# Adafruit_2_4in_TFT_FeatherWing.net
KiCad netlist of a schematic drawn in EAGLE
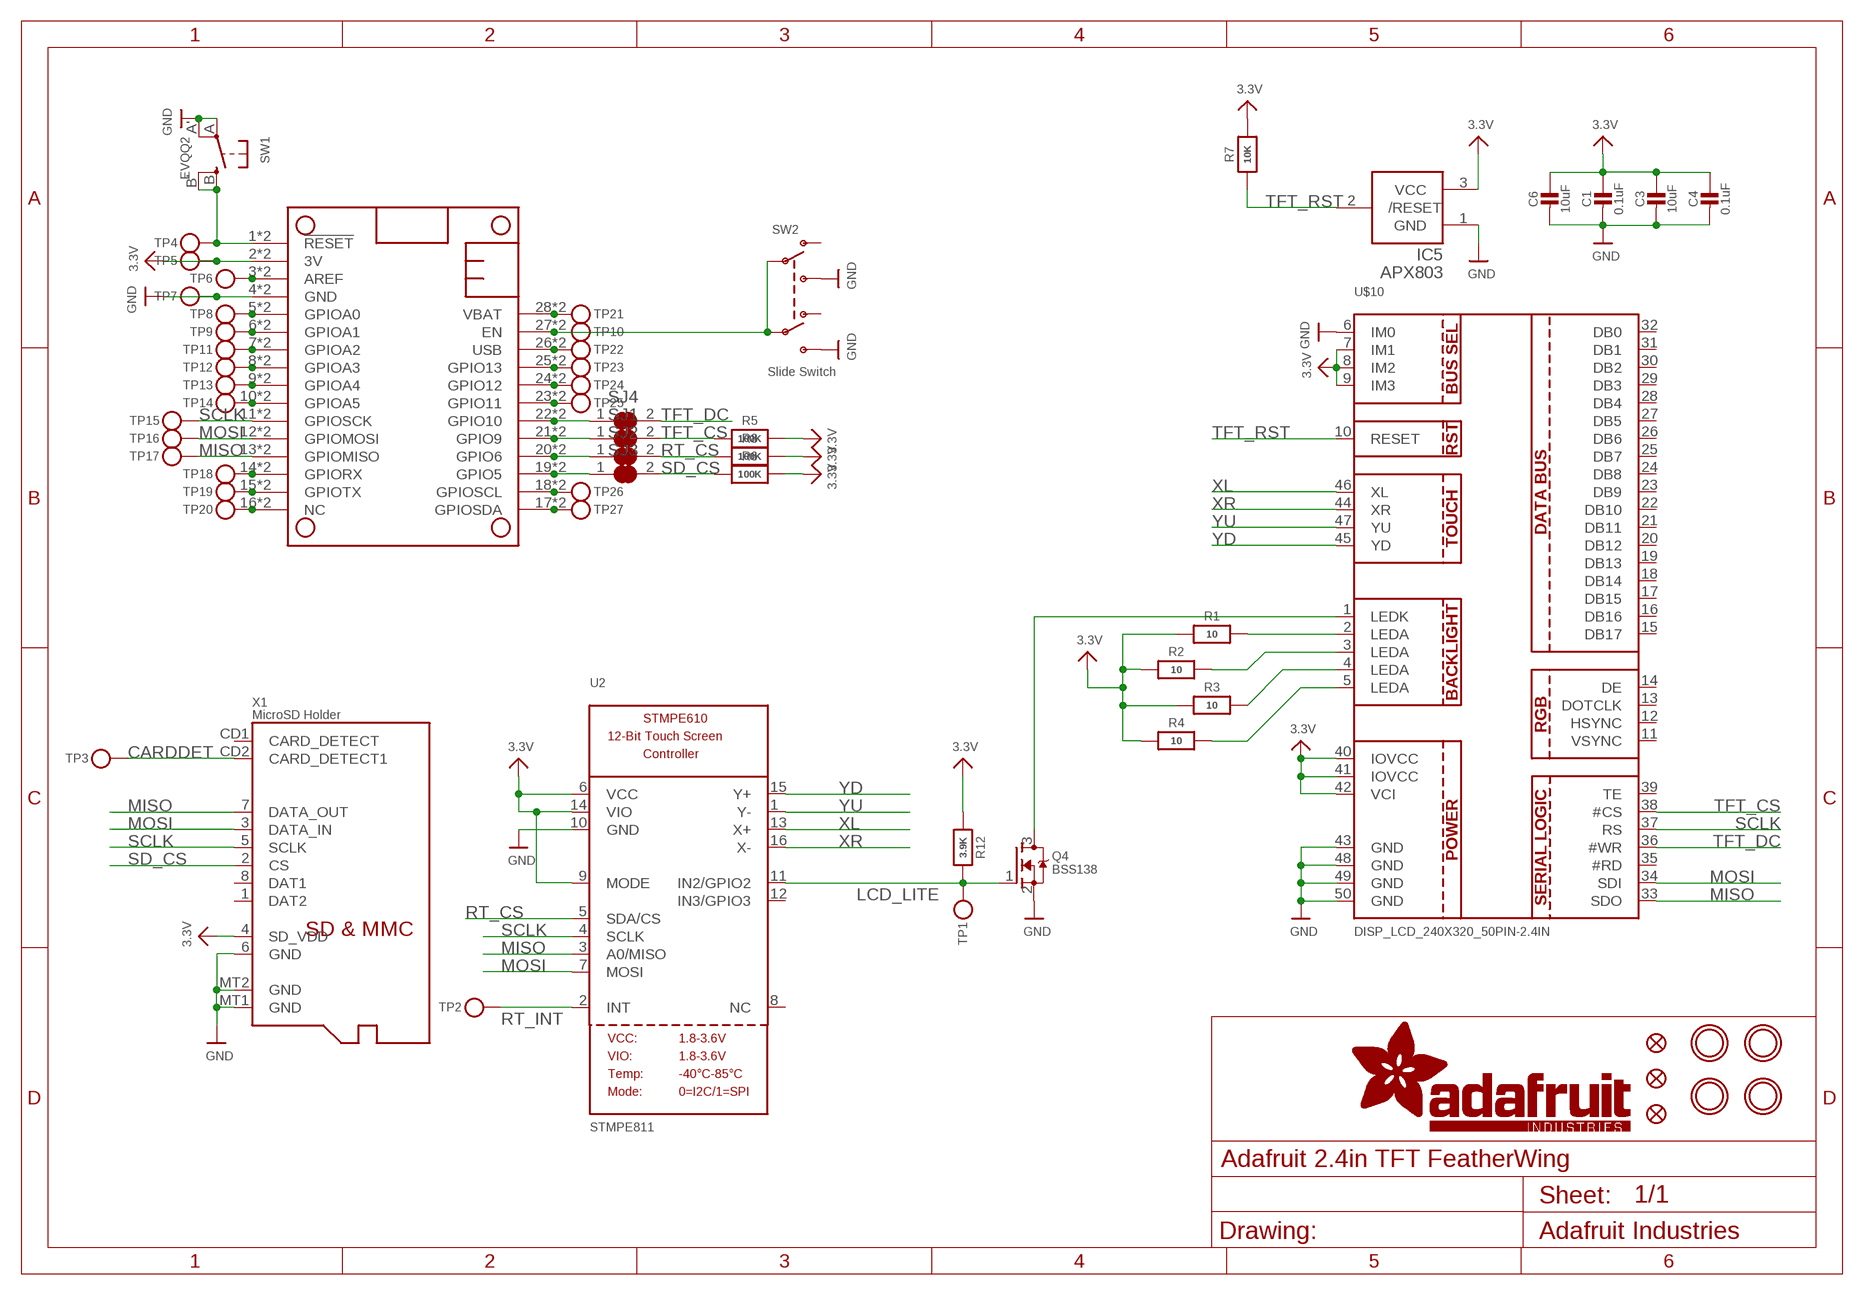
[diagram p0: schematic, sheet 1]

(export (version "E")
  (design (tool "Eeschema 10.0.6"))
  (components
    (comp (ref "C1")
      (value "0.1uF")
      (footprint "eagle-import:0805-NO")
      (libsource (lib "eagle-import") (part "CAP_CERAMIC0805-NOOUTLINE"))
    )
    (comp (ref "C3")
      (value "10uF")
      (footprint "eagle-import:0805-NO")
      (libsource (lib "eagle-import") (part "CAP_CERAMIC0805-NOOUTLINE"))
    )
    (comp (ref "C4")
      (value "0.1uF")
      (footprint "eagle-import:0805-NO")
      (libsource (lib "eagle-import") (part "CAP_CERAMIC0805-NOOUTLINE"))
    )
    (comp (ref "C6")
      (value "10uF")
      (footprint "eagle-import:0805-NO")
      (libsource (lib "eagle-import") (part "CAP_CERAMIC0805-NOOUTLINE"))
    )
    (comp (ref "FID1")
      (value "FIDUCIAL\"\"")
      (footprint "eagle-import:FIDUCIAL_1MM")
      (libsource (lib "eagle-import") (part "FIDUCIAL{dblquote}{dblquote}"))
    )
    (comp (ref "FID2")
      (value "FIDUCIAL\"\"")
      (footprint "eagle-import:FIDUCIAL_1MM")
      (libsource (lib "eagle-import") (part "FIDUCIAL{dblquote}{dblquote}"))
    )
    (comp (ref "FID3")
      (value "FIDUCIAL\"\"")
      (footprint "eagle-import:FIDUCIAL_1MM")
      (libsource (lib "eagle-import") (part "FIDUCIAL{dblquote}{dblquote}"))
    )
    (comp (ref "IC5")
      (value "APX803")
      (footprint "eagle-import:SOT23")
      (libsource (lib "eagle-import") (part "AXP083-SAG"))
    )
    (comp (ref "MS2")
      (value "FEATHERWING_SMTDUAL")
      (footprint "eagle-import:FEATHERWING_SMT2")
      (libsource (lib "eagle-import") (part "FEATHERWING_SMTDUAL"))
    )
    (comp (ref "Q4")
      (value "BSS138")
      (footprint "eagle-import:SOT23-WIDE")
      (libsource (lib "eagle-import") (part "MOSFET-NWIDE"))
    )
    (comp (ref "R1")
      (value "10")
      (footprint "eagle-import:0805-NO")
      (libsource (lib "eagle-import") (part "RESISTOR0805_NOOUTLINE"))
    )
    (comp (ref "R2")
      (value "10")
      (footprint "eagle-import:0805-NO")
      (libsource (lib "eagle-import") (part "RESISTOR0805_NOOUTLINE"))
    )
    (comp (ref "R3")
      (value "10")
      (footprint "eagle-import:0805-NO")
      (libsource (lib "eagle-import") (part "RESISTOR0805_NOOUTLINE"))
    )
    (comp (ref "R4")
      (value "10")
      (footprint "eagle-import:0805-NO")
      (libsource (lib "eagle-import") (part "RESISTOR0805_NOOUTLINE"))
    )
    (comp (ref "R5")
      (value "100K")
      (footprint "eagle-import:0805-NO")
      (libsource (lib "eagle-import") (part "RESISTOR0805_NOOUTLINE"))
    )
    (comp (ref "R6")
      (value "100K")
      (footprint "eagle-import:0805-NO")
      (libsource (lib "eagle-import") (part "RESISTOR0805_NOOUTLINE"))
    )
    (comp (ref "R7")
      (value "10K")
      (footprint "eagle-import:0805-NO")
      (libsource (lib "eagle-import") (part "RESISTOR0805_NOOUTLINE"))
    )
    (comp (ref "R8")
      (value "100K")
      (footprint "eagle-import:0805-NO")
      (libsource (lib "eagle-import") (part "RESISTOR0805_NOOUTLINE"))
    )
    (comp (ref "R12")
      (value "3.9K")
      (footprint "eagle-import:0805-NO")
      (libsource (lib "eagle-import") (part "RESISTOR0805_NOOUTLINE"))
    )
    (comp (ref "SJ1")
      (value "SOLDERJUMPER_CLOSED")
      (footprint "eagle-import:SOLDERJUMPER_CLOSEDWIRE")
      (libsource (lib "eagle-import") (part "SOLDERJUMPER_CLOSED"))
    )
    (comp (ref "SJ2")
      (value "SOLDERJUMPER_CLOSED")
      (footprint "eagle-import:SOLDERJUMPER_CLOSEDWIRE")
      (libsource (lib "eagle-import") (part "SOLDERJUMPER_CLOSED"))
    )
    (comp (ref "SJ3")
      (value "SOLDERJUMPER_CLOSED")
      (footprint "eagle-import:SOLDERJUMPER_CLOSEDWIRE")
      (libsource (lib "eagle-import") (part "SOLDERJUMPER_CLOSED"))
    )
    (comp (ref "SJ4")
      (value "SOLDERJUMPER_CLOSED")
      (footprint "eagle-import:SOLDERJUMPER_CLOSEDWIRE")
      (libsource (lib "eagle-import") (part "SOLDERJUMPER_CLOSED"))
    )
    (comp (ref "SW1")
      (value "EVQQ2")
      (footprint "eagle-import:EVQ-Q2_SMALLER")
      (libsource (lib "eagle-import") (part "SWITCH_TACT_SMT_EVQQ2_SMALL"))
    )
    (comp (ref "SW2")
      (value "Slide Switch")
      (footprint "eagle-import:EG1390")
      (libsource (lib "eagle-import") (part "SWITCH_DPDTEG1390"))
    )
    (comp (ref "TP1")
      (value "TESTPOINTPAD2MM")
      (footprint "eagle-import:TESTPOINT_PAD_2MM")
      (libsource (lib "eagle-import") (part "TESTPOINTPAD2MM"))
    )
    (comp (ref "TP2")
      (value "TESTPOINTPAD2MM")
      (footprint "eagle-import:TESTPOINT_PAD_2MM")
      (libsource (lib "eagle-import") (part "TESTPOINTPAD2MM"))
    )
    (comp (ref "TP3")
      (value "TESTPOINTPAD2MM")
      (footprint "eagle-import:TESTPOINT_PAD_2MM")
      (libsource (lib "eagle-import") (part "TESTPOINTPAD2MM"))
    )
    (comp (ref "TP4")
      (value "TESTPOINTPAD2MM")
      (footprint "eagle-import:TESTPOINT_PAD_2MM")
      (libsource (lib "eagle-import") (part "TESTPOINTPAD2MM"))
    )
    (comp (ref "TP5")
      (value "TESTPOINTPAD2MM")
      (footprint "eagle-import:TESTPOINT_PAD_2MM")
      (libsource (lib "eagle-import") (part "TESTPOINTPAD2MM"))
    )
    (comp (ref "TP6")
      (value "TESTPOINTPAD2MM")
      (footprint "eagle-import:TESTPOINT_PAD_2MM")
      (libsource (lib "eagle-import") (part "TESTPOINTPAD2MM"))
    )
    (comp (ref "TP7")
      (value "TESTPOINTPAD2MM")
      (footprint "eagle-import:TESTPOINT_PAD_2MM")
      (libsource (lib "eagle-import") (part "TESTPOINTPAD2MM"))
    )
    (comp (ref "TP8")
      (value "TESTPOINTPAD2MM")
      (footprint "eagle-import:TESTPOINT_PAD_2MM")
      (libsource (lib "eagle-import") (part "TESTPOINTPAD2MM"))
    )
    (comp (ref "TP9")
      (value "TESTPOINTPAD2MM")
      (footprint "eagle-import:TESTPOINT_PAD_2MM")
      (libsource (lib "eagle-import") (part "TESTPOINTPAD2MM"))
    )
    (comp (ref "TP10")
      (value "TESTPOINTPAD2MM")
      (footprint "eagle-import:TESTPOINT_PAD_2MM")
      (libsource (lib "eagle-import") (part "TESTPOINTPAD2MM"))
    )
    (comp (ref "TP11")
      (value "TESTPOINTPAD2MM")
      (footprint "eagle-import:TESTPOINT_PAD_2MM")
      (libsource (lib "eagle-import") (part "TESTPOINTPAD2MM"))
    )
    (comp (ref "TP12")
      (value "TESTPOINTPAD2MM")
      (footprint "eagle-import:TESTPOINT_PAD_2MM")
      (libsource (lib "eagle-import") (part "TESTPOINTPAD2MM"))
    )
    (comp (ref "TP13")
      (value "TESTPOINTPAD2MM")
      (footprint "eagle-import:TESTPOINT_PAD_2MM")
      (libsource (lib "eagle-import") (part "TESTPOINTPAD2MM"))
    )
    (comp (ref "TP14")
      (value "TESTPOINTPAD2MM")
      (footprint "eagle-import:TESTPOINT_PAD_2MM")
      (libsource (lib "eagle-import") (part "TESTPOINTPAD2MM"))
    )
    (comp (ref "TP15")
      (value "TESTPOINTPAD2MM")
      (footprint "eagle-import:TESTPOINT_PAD_2MM")
      (libsource (lib "eagle-import") (part "TESTPOINTPAD2MM"))
    )
    (comp (ref "TP16")
      (value "TESTPOINTPAD2MM")
      (footprint "eagle-import:TESTPOINT_PAD_2MM")
      (libsource (lib "eagle-import") (part "TESTPOINTPAD2MM"))
    )
    (comp (ref "TP17")
      (value "TESTPOINTPAD2MM")
      (footprint "eagle-import:TESTPOINT_PAD_2MM")
      (libsource (lib "eagle-import") (part "TESTPOINTPAD2MM"))
    )
    (comp (ref "TP18")
      (value "TESTPOINTPAD2MM")
      (footprint "eagle-import:TESTPOINT_PAD_2MM")
      (libsource (lib "eagle-import") (part "TESTPOINTPAD2MM"))
    )
    (comp (ref "TP19")
      (value "TESTPOINTPAD2MM")
      (footprint "eagle-import:TESTPOINT_PAD_2MM")
      (libsource (lib "eagle-import") (part "TESTPOINTPAD2MM"))
    )
    (comp (ref "TP20")
      (value "TESTPOINTPAD2MM")
      (footprint "eagle-import:TESTPOINT_PAD_2MM")
      (libsource (lib "eagle-import") (part "TESTPOINTPAD2MM"))
    )
    (comp (ref "TP21")
      (value "TESTPOINTPAD2MM")
      (footprint "eagle-import:TESTPOINT_PAD_2MM")
      (libsource (lib "eagle-import") (part "TESTPOINTPAD2MM"))
    )
    (comp (ref "TP22")
      (value "TESTPOINTPAD2MM")
      (footprint "eagle-import:TESTPOINT_PAD_2MM")
      (libsource (lib "eagle-import") (part "TESTPOINTPAD2MM"))
    )
    (comp (ref "TP23")
      (value "TESTPOINTPAD2MM")
      (footprint "eagle-import:TESTPOINT_PAD_2MM")
      (libsource (lib "eagle-import") (part "TESTPOINTPAD2MM"))
    )
    (comp (ref "TP24")
      (value "TESTPOINTPAD2MM")
      (footprint "eagle-import:TESTPOINT_PAD_2MM")
      (libsource (lib "eagle-import") (part "TESTPOINTPAD2MM"))
    )
    (comp (ref "TP25")
      (value "TESTPOINTPAD2MM")
      (footprint "eagle-import:TESTPOINT_PAD_2MM")
      (libsource (lib "eagle-import") (part "TESTPOINTPAD2MM"))
    )
    (comp (ref "TP26")
      (value "TESTPOINTPAD2MM")
      (footprint "eagle-import:TESTPOINT_PAD_2MM")
      (libsource (lib "eagle-import") (part "TESTPOINTPAD2MM"))
    )
    (comp (ref "TP27")
      (value "TESTPOINTPAD2MM")
      (footprint "eagle-import:TESTPOINT_PAD_2MM")
      (libsource (lib "eagle-import") (part "TESTPOINTPAD2MM"))
    )
    (comp (ref "U$9")
      (value "MOUNTINGHOLE2.5")
      (footprint "eagle-import:MOUNTINGHOLE_2.5_PLATED")
      (libsource (lib "eagle-import") (part "MOUNTINGHOLE2.5"))
    )
    (comp (ref "U$10")
      (value "DISP_LCD_240X320_50PIN-2.4IN")
      (footprint "eagle-import:TFT_2.4IN_240X320_50PIN")
      (libsource (lib "eagle-import") (part "DISP_LCD_240X320_50PIN-2.4IN"))
    )
    (comp (ref "U$11")
      (value "MOUNTINGHOLE2.5")
      (footprint "eagle-import:MOUNTINGHOLE_2.5_PLATED")
      (libsource (lib "eagle-import") (part "MOUNTINGHOLE2.5"))
    )
    (comp (ref "U$15")
      (value "MOUNTINGHOLE2.5")
      (footprint "eagle-import:MOUNTINGHOLE_2.5_PLATED")
      (libsource (lib "eagle-import") (part "MOUNTINGHOLE2.5"))
    )
    (comp (ref "U$17")
      (value "MOUNTINGHOLE2.5")
      (footprint "eagle-import:MOUNTINGHOLE_2.5_PLATED")
      (libsource (lib "eagle-import") (part "MOUNTINGHOLE2.5"))
    )
    (comp (ref "U2")
      (value "STMPE811")
      (footprint "eagle-import:QFN16_3MM")
      (libsource (lib "eagle-import") (part "STMPE610"))
    )
    (comp (ref "X1")
      (value "MicroSD Holder")
      (footprint "eagle-import:MICROSD")
      (libsource (lib "eagle-import") (part "MICROSD"))
    )
  )
  (nets
    (net (code "1") (name "/CARDDET") (class "Default")
      (node (ref "TP3") (pin "P$1") (pinfunction "P$1_P$1") (pintype "bidirectional"))
      (node (ref "X1") (pin "CD2") (pinfunction "CARD_DETECT1_CD2") (pintype "passive"))
    )
    (net (code "2") (name "/LCD_LITE") (class "Default")
      (node (ref "Q4") (pin "1") (pinfunction "G_1") (pintype "bidirectional"))
      (node (ref "R12") (pin "2") (pinfunction "2_2") (pintype "passive"))
      (node (ref "TP1") (pin "P$1") (pinfunction "P$1_P$1") (pintype "bidirectional"))
      (node (ref "U2") (pin "11") (pinfunction "IN2/GPIO2_11") (pintype "bidirectional"))
    )
    (net (code "3") (name "/MISO") (class "Default")
      (node (ref "MS2") (pin "13") (pinfunction "GPIOMISO_13") (pintype "bidirectional"))
      (node (ref "MS2") (pin "13'") (pinfunction "GPIOMISO_13'") (pintype "bidirectional"))
      (node (ref "TP17") (pin "P$1") (pinfunction "P$1_P$1") (pintype "bidirectional"))
      (node (ref "U$10") (pin "33") (pinfunction "SDO_33") (pintype "bidirectional"))
      (node (ref "U2") (pin "3") (pinfunction "A0/MISO_3") (pintype "bidirectional"))
      (node (ref "X1") (pin "7") (pinfunction "DATA_OUT_7") (pintype "output"))
    )
    (net (code "4") (name "/MOSI") (class "Default")
      (node (ref "MS2") (pin "12") (pinfunction "GPIOMOSI_12") (pintype "bidirectional"))
      (node (ref "MS2") (pin "12'") (pinfunction "GPIOMOSI_12'") (pintype "bidirectional"))
      (node (ref "TP16") (pin "P$1") (pinfunction "P$1_P$1") (pintype "bidirectional"))
      (node (ref "U$10") (pin "34") (pinfunction "SDI_34") (pintype "bidirectional"))
      (node (ref "U2") (pin "7") (pinfunction "MOSI_7") (pintype "input"))
      (node (ref "X1") (pin "3") (pinfunction "DATA_IN_3") (pintype "input"))
    )
    (net (code "5") (name "/RT_CS") (class "Default")
      (node (ref "R8") (pin "1") (pinfunction "1_1") (pintype "passive"))
      (node (ref "SJ2") (pin "2") (pinfunction "2_2") (pintype "passive"))
      (node (ref "U2") (pin "5") (pinfunction "SDA/CS_5") (pintype "bidirectional"))
    )
    (net (code "6") (name "/RT_INT") (class "Default")
      (node (ref "TP2") (pin "P$1") (pinfunction "P$1_P$1") (pintype "bidirectional"))
      (node (ref "U2") (pin "2") (pinfunction "INT_2") (pintype "output"))
    )
    (net (code "7") (name "/SCLK") (class "Default")
      (node (ref "MS2") (pin "11") (pinfunction "GPIOSCK_11") (pintype "bidirectional"))
      (node (ref "MS2") (pin "11'") (pinfunction "GPIOSCK_11'") (pintype "bidirectional"))
      (node (ref "TP15") (pin "P$1") (pinfunction "P$1_P$1") (pintype "bidirectional"))
      (node (ref "U$10") (pin "37") (pinfunction "RS_37") (pintype "bidirectional"))
      (node (ref "U2") (pin "4") (pinfunction "SCLK_4") (pintype "bidirectional"))
      (node (ref "X1") (pin "5") (pinfunction "SCLK_5") (pintype "input"))
    )
    (net (code "8") (name "/SD_CS") (class "Default")
      (node (ref "R6") (pin "1") (pinfunction "1_1") (pintype "passive"))
      (node (ref "SJ3") (pin "2") (pinfunction "2_2") (pintype "passive"))
      (node (ref "X1") (pin "2") (pinfunction "CS_2") (pintype "input"))
    )
    (net (code "9") (name "/TFT_CS") (class "Default")
      (node (ref "R5") (pin "1") (pinfunction "1_1") (pintype "passive"))
      (node (ref "SJ1") (pin "2") (pinfunction "2_2") (pintype "passive"))
      (node (ref "U$10") (pin "38") (pinfunction "#CS_38") (pintype "bidirectional"))
    )
    (net (code "10") (name "/TFT_DC") (class "Default")
      (node (ref "SJ4") (pin "2") (pinfunction "2_2") (pintype "passive"))
      (node (ref "U$10") (pin "36") (pinfunction "#WR_36") (pintype "bidirectional"))
    )
    (net (code "11") (name "/TFT_RST") (class "Default")
      (node (ref "IC5") (pin "2") (pinfunction "/RESET_2") (pintype "output"))
      (node (ref "R7") (pin "1") (pinfunction "1_1") (pintype "passive"))
      (node (ref "U$10") (pin "10") (pinfunction "RESET_10") (pintype "bidirectional"))
    )
    (net (code "12") (name "/XL") (class "Default")
      (node (ref "U$10") (pin "46") (pinfunction "XL_46") (pintype "bidirectional"))
      (node (ref "U2") (pin "13") (pinfunction "X+_13") (pintype "input"))
    )
    (net (code "13") (name "/XR") (class "Default")
      (node (ref "U$10") (pin "44") (pinfunction "XR_44") (pintype "bidirectional"))
      (node (ref "U2") (pin "16") (pinfunction "X-_16") (pintype "input"))
    )
    (net (code "14") (name "/YD") (class "Default")
      (node (ref "U$10") (pin "45") (pinfunction "YD_45") (pintype "bidirectional"))
      (node (ref "U2") (pin "15") (pinfunction "Y+_15") (pintype "input"))
    )
    (net (code "15") (name "/YU") (class "Default")
      (node (ref "U$10") (pin "47") (pinfunction "YU_47") (pintype "bidirectional"))
      (node (ref "U2") (pin "1") (pinfunction "Y-_1") (pintype "input"))
    )
    (net (code "16") (name "3.3V") (class "Default")
      (node (ref "C1") (pin "1") (pinfunction "1_1") (pintype "passive"))
      (node (ref "C3") (pin "1") (pinfunction "1_1") (pintype "passive"))
      (node (ref "C4") (pin "1") (pinfunction "1_1") (pintype "passive"))
      (node (ref "C6") (pin "1") (pinfunction "1_1") (pintype "passive"))
      (node (ref "IC5") (pin "3") (pinfunction "VCC_3") (pintype "power_in"))
      (node (ref "MS2") (pin "2") (pinfunction "3V_2") (pintype "power_in"))
      (node (ref "MS2") (pin "2'") (pinfunction "3V_2'") (pintype "power_in"))
      (node (ref "R1") (pin "1") (pinfunction "1_1") (pintype "passive"))
      (node (ref "R12") (pin "1") (pinfunction "1_1") (pintype "passive"))
      (node (ref "R2") (pin "1") (pinfunction "1_1") (pintype "passive"))
      (node (ref "R3") (pin "1") (pinfunction "1_1") (pintype "passive"))
      (node (ref "R4") (pin "1") (pinfunction "1_1") (pintype "passive"))
      (node (ref "R5") (pin "2") (pinfunction "2_2") (pintype "passive"))
      (node (ref "R6") (pin "2") (pinfunction "2_2") (pintype "passive"))
      (node (ref "R7") (pin "2") (pinfunction "2_2") (pintype "passive"))
      (node (ref "R8") (pin "2") (pinfunction "2_2") (pintype "passive"))
      (node (ref "TP5") (pin "P$1") (pinfunction "P$1_P$1") (pintype "bidirectional"))
      (node (ref "U$10") (pin "40") (pinfunction "IOVCC_40") (pintype "bidirectional"))
      (node (ref "U$10") (pin "41") (pinfunction "IOVCC_41") (pintype "bidirectional"))
      (node (ref "U$10") (pin "42") (pinfunction "VCI_42") (pintype "bidirectional"))
      (node (ref "U$10") (pin "7") (pinfunction "IM1_7") (pintype "bidirectional"))
      (node (ref "U$10") (pin "8") (pinfunction "IM2_8") (pintype "bidirectional"))
      (node (ref "U$10") (pin "9") (pinfunction "IM3_9") (pintype "bidirectional"))
      (node (ref "U2") (pin "14") (pinfunction "VIO_14") (pintype "power_in"))
      (node (ref "U2") (pin "6") (pinfunction "VCC_6") (pintype "power_in"))
      (node (ref "U2") (pin "9") (pinfunction "MODE_9") (pintype "input"))
      (node (ref "X1") (pin "4") (pinfunction "SD_VDD_4") (pintype "power_in"))
    )
    (net (code "17") (name "GND") (class "Default")
      (node (ref "C1") (pin "2") (pinfunction "2_2") (pintype "passive"))
      (node (ref "C3") (pin "2") (pinfunction "2_2") (pintype "passive"))
      (node (ref "C4") (pin "2") (pinfunction "2_2") (pintype "passive"))
      (node (ref "C6") (pin "2") (pinfunction "2_2") (pintype "passive"))
      (node (ref "IC5") (pin "1") (pinfunction "GND_1") (pintype "power_in"))
      (node (ref "MS2") (pin "4") (pinfunction "GND_4") (pintype "power_in"))
      (node (ref "MS2") (pin "4'") (pinfunction "GND_4'") (pintype "power_in"))
      (node (ref "Q4") (pin "2") (pinfunction "S_2") (pintype "bidirectional"))
      (node (ref "SW1") (pin "A") (pinfunction "P_A") (pintype "passive"))
      (node (ref "SW1") (pin "A'") (pinfunction "P1_A'") (pintype "passive"))
      (node (ref "SW2") (pin "S1") (pinfunction "S1_S1") (pintype "passive"))
      (node (ref "SW2") (pin "S2") (pinfunction "S2_S2") (pintype "passive"))
      (node (ref "TP7") (pin "P$1") (pinfunction "P$1_P$1") (pintype "bidirectional"))
      (node (ref "U$10") (pin "43") (pinfunction "GND_43") (pintype "bidirectional"))
      (node (ref "U$10") (pin "48") (pinfunction "GND_48") (pintype "bidirectional"))
      (node (ref "U$10") (pin "49") (pinfunction "GND_49") (pintype "bidirectional"))
      (node (ref "U$10") (pin "50") (pinfunction "GND_50") (pintype "bidirectional"))
      (node (ref "U$10") (pin "6") (pinfunction "IM0_6") (pintype "bidirectional"))
      (node (ref "U2") (pin "10") (pinfunction "GND_10") (pintype "power_in"))
      (node (ref "X1") (pin "6") (pinfunction "GND_6") (pintype "power_in"))
      (node (ref "X1") (pin "MT1") (pinfunction "GND_MT1") (pintype "power_in"))
      (node (ref "X1") (pin "MT2") (pinfunction "GND_MT2") (pintype "power_in"))
    )
    (net (code "18") (name "Net-(MS2-AREF-Pad3')") (class "Default")
      (node (ref "MS2") (pin "3") (pinfunction "AREF_3") (pintype "passive"))
      (node (ref "MS2") (pin "3'") (pinfunction "AREF_3'") (pintype "passive"))
      (node (ref "TP6") (pin "P$1") (pinfunction "P$1_P$1") (pintype "bidirectional"))
    )
    (net (code "19") (name "Net-(MS2-EN-Pad27')") (class "Default")
      (node (ref "MS2") (pin "27") (pinfunction "EN_27") (pintype "passive"))
      (node (ref "MS2") (pin "27'") (pinfunction "EN_27'") (pintype "passive"))
      (node (ref "SW2") (pin "P1") (pinfunction "P1_P1") (pintype "passive"))
      (node (ref "SW2") (pin "P2") (pinfunction "P2_P2") (pintype "passive"))
      (node (ref "TP10") (pin "P$1") (pinfunction "P$1_P$1") (pintype "bidirectional"))
    )
    (net (code "20") (name "Net-(MS2-GPIO5-Pad19')") (class "Default")
      (node (ref "MS2") (pin "19") (pinfunction "GPIO5_19") (pintype "bidirectional"))
      (node (ref "MS2") (pin "19'") (pinfunction "GPIO5_19'") (pintype "bidirectional"))
      (node (ref "SJ3") (pin "1") (pinfunction "1_1") (pintype "passive"))
    )
    (net (code "21") (name "Net-(MS2-GPIO6-Pad20')") (class "Default")
      (node (ref "MS2") (pin "20") (pinfunction "GPIO6_20") (pintype "bidirectional"))
      (node (ref "MS2") (pin "20'") (pinfunction "GPIO6_20'") (pintype "bidirectional"))
      (node (ref "SJ2") (pin "1") (pinfunction "1_1") (pintype "passive"))
    )
    (net (code "22") (name "Net-(MS2-GPIO9-Pad21')") (class "Default")
      (node (ref "MS2") (pin "21") (pinfunction "GPIO9_21") (pintype "bidirectional"))
      (node (ref "MS2") (pin "21'") (pinfunction "GPIO9_21'") (pintype "bidirectional"))
      (node (ref "SJ1") (pin "1") (pinfunction "1_1") (pintype "passive"))
    )
    (net (code "23") (name "Net-(MS2-GPIO10-Pad22')") (class "Default")
      (node (ref "MS2") (pin "22") (pinfunction "GPIO10_22") (pintype "bidirectional"))
      (node (ref "MS2") (pin "22'") (pinfunction "GPIO10_22'") (pintype "bidirectional"))
      (node (ref "SJ4") (pin "1") (pinfunction "1_1") (pintype "passive"))
    )
    (net (code "24") (name "Net-(MS2-GPIO11-Pad23')") (class "Default")
      (node (ref "MS2") (pin "23") (pinfunction "GPIO11_23") (pintype "bidirectional"))
      (node (ref "MS2") (pin "23'") (pinfunction "GPIO11_23'") (pintype "bidirectional"))
      (node (ref "TP25") (pin "P$1") (pinfunction "P$1_P$1") (pintype "bidirectional"))
    )
    (net (code "25") (name "Net-(MS2-GPIO12-Pad24')") (class "Default")
      (node (ref "MS2") (pin "24") (pinfunction "GPIO12_24") (pintype "bidirectional"))
      (node (ref "MS2") (pin "24'") (pinfunction "GPIO12_24'") (pintype "bidirectional"))
      (node (ref "TP24") (pin "P$1") (pinfunction "P$1_P$1") (pintype "bidirectional"))
    )
    (net (code "26") (name "Net-(MS2-GPIO13-Pad25')") (class "Default")
      (node (ref "MS2") (pin "25") (pinfunction "GPIO13_25") (pintype "bidirectional"))
      (node (ref "MS2") (pin "25'") (pinfunction "GPIO13_25'") (pintype "bidirectional"))
      (node (ref "TP23") (pin "P$1") (pinfunction "P$1_P$1") (pintype "bidirectional"))
    )
    (net (code "27") (name "Net-(MS2-GPIOA0-Pad5')") (class "Default")
      (node (ref "MS2") (pin "5") (pinfunction "GPIOA0_5") (pintype "bidirectional"))
      (node (ref "MS2") (pin "5'") (pinfunction "GPIOA0_5'") (pintype "bidirectional"))
      (node (ref "TP8") (pin "P$1") (pinfunction "P$1_P$1") (pintype "bidirectional"))
    )
    (net (code "28") (name "Net-(MS2-GPIOA1-Pad6')") (class "Default")
      (node (ref "MS2") (pin "6") (pinfunction "GPIOA1_6") (pintype "bidirectional"))
      (node (ref "MS2") (pin "6'") (pinfunction "GPIOA1_6'") (pintype "bidirectional"))
      (node (ref "TP9") (pin "P$1") (pinfunction "P$1_P$1") (pintype "bidirectional"))
    )
    (net (code "29") (name "Net-(MS2-GPIOA2-Pad7')") (class "Default")
      (node (ref "MS2") (pin "7") (pinfunction "GPIOA2_7") (pintype "bidirectional"))
      (node (ref "MS2") (pin "7'") (pinfunction "GPIOA2_7'") (pintype "bidirectional"))
      (node (ref "TP11") (pin "P$1") (pinfunction "P$1_P$1") (pintype "bidirectional"))
    )
    (net (code "30") (name "Net-(MS2-GPIOA3-Pad8')") (class "Default")
      (node (ref "MS2") (pin "8") (pinfunction "GPIOA3_8") (pintype "bidirectional"))
      (node (ref "MS2") (pin "8'") (pinfunction "GPIOA3_8'") (pintype "bidirectional"))
      (node (ref "TP12") (pin "P$1") (pinfunction "P$1_P$1") (pintype "bidirectional"))
    )
    (net (code "31") (name "Net-(MS2-GPIOA4-Pad9')") (class "Default")
      (node (ref "MS2") (pin "9") (pinfunction "GPIOA4_9") (pintype "bidirectional"))
      (node (ref "MS2") (pin "9'") (pinfunction "GPIOA4_9'") (pintype "bidirectional"))
      (node (ref "TP13") (pin "P$1") (pinfunction "P$1_P$1") (pintype "bidirectional"))
    )
    (net (code "32") (name "Net-(MS2-GPIOA5-Pad10')") (class "Default")
      (node (ref "MS2") (pin "10") (pinfunction "GPIOA5_10") (pintype "bidirectional"))
      (node (ref "MS2") (pin "10'") (pinfunction "GPIOA5_10'") (pintype "bidirectional"))
      (node (ref "TP14") (pin "P$1") (pinfunction "P$1_P$1") (pintype "bidirectional"))
    )
    (net (code "33") (name "Net-(MS2-GPIORX-Pad14')") (class "Default")
      (node (ref "MS2") (pin "14") (pinfunction "GPIORX_14") (pintype "bidirectional"))
      (node (ref "MS2") (pin "14'") (pinfunction "GPIORX_14'") (pintype "bidirectional"))
      (node (ref "TP18") (pin "P$1") (pinfunction "P$1_P$1") (pintype "bidirectional"))
    )
    (net (code "34") (name "Net-(MS2-GPIOSCL-Pad18')") (class "Default")
      (node (ref "MS2") (pin "18") (pinfunction "GPIOSCL_18") (pintype "bidirectional"))
      (node (ref "MS2") (pin "18'") (pinfunction "GPIOSCL_18'") (pintype "bidirectional"))
      (node (ref "TP26") (pin "P$1") (pinfunction "P$1_P$1") (pintype "bidirectional"))
    )
    (net (code "35") (name "Net-(MS2-GPIOSDA-Pad17')") (class "Default")
      (node (ref "MS2") (pin "17") (pinfunction "GPIOSDA_17") (pintype "bidirectional"))
      (node (ref "MS2") (pin "17'") (pinfunction "GPIOSDA_17'") (pintype "bidirectional"))
      (node (ref "TP27") (pin "P$1") (pinfunction "P$1_P$1") (pintype "bidirectional"))
    )
    (net (code "36") (name "Net-(MS2-GPIOTX-Pad15')") (class "Default")
      (node (ref "MS2") (pin "15") (pinfunction "GPIOTX_15") (pintype "bidirectional"))
      (node (ref "MS2") (pin "15'") (pinfunction "GPIOTX_15'") (pintype "bidirectional"))
      (node (ref "TP19") (pin "P$1") (pinfunction "P$1_P$1") (pintype "bidirectional"))
    )
    (net (code "37") (name "Net-(MS2-NC-Pad16')") (class "Default")
      (node (ref "MS2") (pin "16") (pinfunction "NC_16") (pintype "passive"))
      (node (ref "MS2") (pin "16'") (pinfunction "NC_16'") (pintype "passive"))
      (node (ref "TP20") (pin "P$1") (pinfunction "P$1_P$1") (pintype "bidirectional"))
    )
    (net (code "38") (name "Net-(MS2-USB-Pad26')") (class "Default")
      (node (ref "MS2") (pin "26") (pinfunction "USB_26") (pintype "power_in"))
      (node (ref "MS2") (pin "26'") (pinfunction "USB_26'") (pintype "power_in"))
      (node (ref "TP22") (pin "P$1") (pinfunction "P$1_P$1") (pintype "bidirectional"))
    )
    (net (code "39") (name "Net-(MS2-VBAT-Pad28')") (class "Default")
      (node (ref "MS2") (pin "28") (pinfunction "VBAT_28") (pintype "power_in"))
      (node (ref "MS2") (pin "28'") (pinfunction "VBAT_28'") (pintype "power_in"))
      (node (ref "TP21") (pin "P$1") (pinfunction "P$1_P$1") (pintype "bidirectional"))
    )
    (net (code "40") (name "Net-(Q4-D)") (class "Default")
      (node (ref "Q4") (pin "3") (pinfunction "D_3") (pintype "bidirectional"))
      (node (ref "U$10") (pin "1") (pinfunction "LEDK_1") (pintype "bidirectional"))
    )
    (net (code "41") (name "Net-(R1-Pad2)") (class "Default")
      (node (ref "R1") (pin "2") (pinfunction "2_2") (pintype "passive"))
      (node (ref "U$10") (pin "2") (pinfunction "LEDA_2") (pintype "bidirectional"))
    )
    (net (code "42") (name "Net-(R2-Pad2)") (class "Default")
      (node (ref "R2") (pin "2") (pinfunction "2_2") (pintype "passive"))
      (node (ref "U$10") (pin "3") (pinfunction "LEDA_3") (pintype "bidirectional"))
    )
    (net (code "43") (name "Net-(R3-Pad2)") (class "Default")
      (node (ref "R3") (pin "2") (pinfunction "2_2") (pintype "passive"))
      (node (ref "U$10") (pin "4") (pinfunction "LEDA_4") (pintype "bidirectional"))
    )
    (net (code "44") (name "Net-(R4-Pad2)") (class "Default")
      (node (ref "R4") (pin "2") (pinfunction "2_2") (pintype "passive"))
      (node (ref "U$10") (pin "5") (pinfunction "LEDA_5") (pintype "bidirectional"))
    )
    (net (code "45") (name "Net-(SW1-S)") (class "Default")
      (node (ref "MS2") (pin "1") (pinfunction "~{RESET}_1") (pintype "input"))
      (node (ref "MS2") (pin "1'") (pinfunction "~{RESET}_1'") (pintype "input"))
      (node (ref "SW1") (pin "B") (pinfunction "S_B") (pintype "passive"))
      (node (ref "SW1") (pin "B'") (pinfunction "S1_B'") (pintype "passive"))
      (node (ref "TP4") (pin "P$1") (pinfunction "P$1_P$1") (pintype "bidirectional"))
    )
    (net (code "46") (name "unconnected-(SW2-PadO1)") (class "Default")
      (node (ref "SW2") (pin "O1") (pinfunction "O1_O1") (pintype "passive"))
    )
    (net (code "47") (name "unconnected-(SW2-PadO2)") (class "Default")
      (node (ref "SW2") (pin "O2") (pinfunction "O2_O2") (pintype "passive"))
    )
    (net (code "48") (name "unconnected-(U$10-#RD-Pad35)") (class "Default")
      (node (ref "U$10") (pin "35") (pinfunction "#RD_35") (pintype "bidirectional"))
    )
    (net (code "49") (name "unconnected-(U$10-DB0-Pad32)") (class "Default")
      (node (ref "U$10") (pin "32") (pinfunction "DB0_32") (pintype "bidirectional"))
    )
    (net (code "50") (name "unconnected-(U$10-DB1-Pad31)") (class "Default")
      (node (ref "U$10") (pin "31") (pinfunction "DB1_31") (pintype "bidirectional"))
    )
    (net (code "51") (name "unconnected-(U$10-DB2-Pad30)") (class "Default")
      (node (ref "U$10") (pin "30") (pinfunction "DB2_30") (pintype "bidirectional"))
    )
    (net (code "52") (name "unconnected-(U$10-DB3-Pad29)") (class "Default")
      (node (ref "U$10") (pin "29") (pinfunction "DB3_29") (pintype "bidirectional"))
    )
    (net (code "53") (name "unconnected-(U$10-DB4-Pad28)") (class "Default")
      (node (ref "U$10") (pin "28") (pinfunction "DB4_28") (pintype "bidirectional"))
    )
    (net (code "54") (name "unconnected-(U$10-DB5-Pad27)") (class "Default")
      (node (ref "U$10") (pin "27") (pinfunction "DB5_27") (pintype "bidirectional"))
    )
    (net (code "55") (name "unconnected-(U$10-DB6-Pad26)") (class "Default")
      (node (ref "U$10") (pin "26") (pinfunction "DB6_26") (pintype "bidirectional"))
    )
    (net (code "56") (name "unconnected-(U$10-DB7-Pad25)") (class "Default")
      (node (ref "U$10") (pin "25") (pinfunction "DB7_25") (pintype "bidirectional"))
    )
    (net (code "57") (name "unconnected-(U$10-DB8-Pad24)") (class "Default")
      (node (ref "U$10") (pin "24") (pinfunction "DB8_24") (pintype "bidirectional"))
    )
    (net (code "58") (name "unconnected-(U$10-DB9-Pad23)") (class "Default")
      (node (ref "U$10") (pin "23") (pinfunction "DB9_23") (pintype "bidirectional"))
    )
    (net (code "59") (name "unconnected-(U$10-DB10-Pad22)") (class "Default")
      (node (ref "U$10") (pin "22") (pinfunction "DB10_22") (pintype "bidirectional"))
    )
    (net (code "60") (name "unconnected-(U$10-DB11-Pad21)") (class "Default")
      (node (ref "U$10") (pin "21") (pinfunction "DB11_21") (pintype "bidirectional"))
    )
    (net (code "61") (name "unconnected-(U$10-DB12-Pad20)") (class "Default")
      (node (ref "U$10") (pin "20") (pinfunction "DB12_20") (pintype "bidirectional"))
    )
    (net (code "62") (name "unconnected-(U$10-DB13-Pad19)") (class "Default")
      (node (ref "U$10") (pin "19") (pinfunction "DB13_19") (pintype "bidirectional"))
    )
    (net (code "63") (name "unconnected-(U$10-DB14-Pad18)") (class "Default")
      (node (ref "U$10") (pin "18") (pinfunction "DB14_18") (pintype "bidirectional"))
    )
    (net (code "64") (name "unconnected-(U$10-DB15-Pad17)") (class "Default")
      (node (ref "U$10") (pin "17") (pinfunction "DB15_17") (pintype "bidirectional"))
    )
    (net (code "65") (name "unconnected-(U$10-DB16-Pad16)") (class "Default")
      (node (ref "U$10") (pin "16") (pinfunction "DB16_16") (pintype "bidirectional"))
    )
    (net (code "66") (name "unconnected-(U$10-DB17-Pad15)") (class "Default")
      (node (ref "U$10") (pin "15") (pinfunction "DB17_15") (pintype "bidirectional"))
    )
    (net (code "67") (name "unconnected-(U$10-DE-Pad14)") (class "Default")
      (node (ref "U$10") (pin "14") (pinfunction "DE_14") (pintype "bidirectional"))
    )
    (net (code "68") (name "unconnected-(U$10-DOTCLK-Pad13)") (class "Default")
      (node (ref "U$10") (pin "13") (pinfunction "DOTCLK_13") (pintype "bidirectional"))
    )
    (net (code "69") (name "unconnected-(U$10-HSYNC-Pad12)") (class "Default")
      (node (ref "U$10") (pin "12") (pinfunction "HSYNC_12") (pintype "bidirectional"))
    )
    (net (code "70") (name "unconnected-(U$10-TE-Pad39)") (class "Default")
      (node (ref "U$10") (pin "39") (pinfunction "TE_39") (pintype "bidirectional"))
    )
    (net (code "71") (name "unconnected-(U$10-VSYNC-Pad11)") (class "Default")
      (node (ref "U$10") (pin "11") (pinfunction "VSYNC_11") (pintype "bidirectional"))
    )
    (net (code "72") (name "unconnected-(U2-IN3{slash}GPIO3-Pad12)") (class "Default")
      (node (ref "U2") (pin "12") (pinfunction "IN3/GPIO3_12") (pintype "bidirectional"))
    )
    (net (code "73") (name "unconnected-(U2-NC-Pad8)") (class "Default")
      (node (ref "U2") (pin "8") (pinfunction "NC_8") (pintype "no_connect"))
    )
    (net (code "74") (name "unconnected-(X1-CARD_DETECT-PadCD1)") (class "Default")
      (node (ref "X1") (pin "CD1") (pinfunction "CARD_DETECT_CD1") (pintype "passive"))
    )
    (net (code "75") (name "unconnected-(X1-DAT1-Pad8)") (class "Default")
      (node (ref "X1") (pin "8") (pinfunction "DAT1_8") (pintype "bidirectional"))
    )
    (net (code "76") (name "unconnected-(X1-DAT2-Pad1)") (class "Default")
      (node (ref "X1") (pin "1") (pinfunction "DAT2_1") (pintype "bidirectional"))
    )
  )
)
